# SO-8-normal.net
KiCad netlist of a schematic drawn in EAGLE
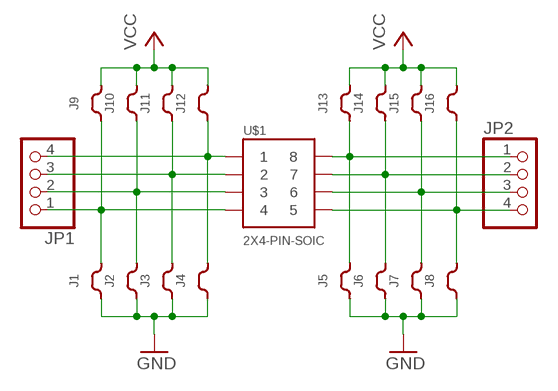
[diagram p0: schematic, sheet 1]

(export (version "E")
  (design (tool "Eeschema 10.0.6"))
  (components
    (comp (ref "J1")
      (value "JUMPER-0805")
      (footprint "eagle-import:RCLJ-0805")
      (libsource (lib "eagle-import") (part "JUMPER-0805"))
    )
    (comp (ref "J2")
      (value "JUMPER-0805")
      (footprint "eagle-import:RCLJ-0805")
      (libsource (lib "eagle-import") (part "JUMPER-0805"))
    )
    (comp (ref "J3")
      (value "JUMPER-0805")
      (footprint "eagle-import:RCLJ-0805")
      (libsource (lib "eagle-import") (part "JUMPER-0805"))
    )
    (comp (ref "J4")
      (value "JUMPER-0805")
      (footprint "eagle-import:RCLJ-0805")
      (libsource (lib "eagle-import") (part "JUMPER-0805"))
    )
    (comp (ref "J5")
      (value "JUMPER-0805")
      (footprint "eagle-import:RCLJ-0805")
      (libsource (lib "eagle-import") (part "JUMPER-0805"))
    )
    (comp (ref "J6")
      (value "JUMPER-0805")
      (footprint "eagle-import:RCLJ-0805")
      (libsource (lib "eagle-import") (part "JUMPER-0805"))
    )
    (comp (ref "J7")
      (value "JUMPER-0805")
      (footprint "eagle-import:RCLJ-0805")
      (libsource (lib "eagle-import") (part "JUMPER-0805"))
    )
    (comp (ref "J8")
      (value "JUMPER-0805")
      (footprint "eagle-import:RCLJ-0805")
      (libsource (lib "eagle-import") (part "JUMPER-0805"))
    )
    (comp (ref "J9")
      (value "JUMPER-0603")
      (footprint "eagle-import:RCLJ-0603")
      (libsource (lib "eagle-import") (part "JUMPER-0603"))
    )
    (comp (ref "J10")
      (value "JUMPER-0603")
      (footprint "eagle-import:RCLJ-0603")
      (libsource (lib "eagle-import") (part "JUMPER-0603"))
    )
    (comp (ref "J11")
      (value "JUMPER-0603")
      (footprint "eagle-import:RCLJ-0603")
      (libsource (lib "eagle-import") (part "JUMPER-0603"))
    )
    (comp (ref "J12")
      (value "JUMPER-0603")
      (footprint "eagle-import:RCLJ-0603")
      (libsource (lib "eagle-import") (part "JUMPER-0603"))
    )
    (comp (ref "J13")
      (value "JUMPER-0603")
      (footprint "eagle-import:RCLJ-0603")
      (libsource (lib "eagle-import") (part "JUMPER-0603"))
    )
    (comp (ref "J14")
      (value "JUMPER-0603")
      (footprint "eagle-import:RCLJ-0603")
      (libsource (lib "eagle-import") (part "JUMPER-0603"))
    )
    (comp (ref "J15")
      (value "JUMPER-0603")
      (footprint "eagle-import:RCLJ-0603")
      (libsource (lib "eagle-import") (part "JUMPER-0603"))
    )
    (comp (ref "J16")
      (value "JUMPER-0603")
      (footprint "eagle-import:RCLJ-0603")
      (libsource (lib "eagle-import") (part "JUMPER-0603"))
    )
    (comp (ref "JP1")
      (value "PINHD-1X4")
      (footprint "eagle-import:1X04")
      (libsource (lib "eagle-import") (part "PINHD-1X4"))
    )
    (comp (ref "JP2")
      (value "PINHD-1X4")
      (footprint "eagle-import:1X04")
      (libsource (lib "eagle-import") (part "PINHD-1X4"))
    )
    (comp (ref "U$1")
      (value "2X4-PIN-SOIC")
      (footprint "eagle-import:SO8")
      (libsource (lib "eagle-import") (part "2X4-PIN-SOIC"))
    )
  )
  (nets
    (net (code "1") (name "GND") (class "Default")
      (node (ref "J1") (pin "1") (pinfunction "P$1_1") (pintype "bidirectional"))
      (node (ref "J2") (pin "1") (pinfunction "P$1_1") (pintype "bidirectional"))
      (node (ref "J3") (pin "1") (pinfunction "P$1_1") (pintype "bidirectional"))
      (node (ref "J4") (pin "1") (pinfunction "P$1_1") (pintype "bidirectional"))
      (node (ref "J5") (pin "1") (pinfunction "P$1_1") (pintype "bidirectional"))
      (node (ref "J6") (pin "1") (pinfunction "P$1_1") (pintype "bidirectional"))
      (node (ref "J7") (pin "1") (pinfunction "P$1_1") (pintype "bidirectional"))
      (node (ref "J8") (pin "1") (pinfunction "P$1_1") (pintype "bidirectional"))
    )
    (net (code "2") (name "Net-(J1-P$2)") (class "Default")
      (node (ref "J1") (pin "2") (pinfunction "P$2_2") (pintype "bidirectional"))
      (node (ref "J9") (pin "1") (pinfunction "P$1_1") (pintype "bidirectional"))
      (node (ref "JP1") (pin "1") (pinfunction "1_1") (pintype "passive"))
      (node (ref "U$1") (pin "P$4") (pinfunction "4_P$4") (pintype "bidirectional"))
    )
    (net (code "3") (name "Net-(J10-P$1)") (class "Default")
      (node (ref "J10") (pin "1") (pinfunction "P$1_1") (pintype "bidirectional"))
      (node (ref "J2") (pin "2") (pinfunction "P$2_2") (pintype "bidirectional"))
      (node (ref "JP1") (pin "2") (pinfunction "2_2") (pintype "passive"))
      (node (ref "U$1") (pin "P$3") (pinfunction "3_P$3") (pintype "bidirectional"))
    )
    (net (code "4") (name "Net-(J11-P$1)") (class "Default")
      (node (ref "J11") (pin "1") (pinfunction "P$1_1") (pintype "bidirectional"))
      (node (ref "J3") (pin "2") (pinfunction "P$2_2") (pintype "bidirectional"))
      (node (ref "JP1") (pin "3") (pinfunction "3_3") (pintype "passive"))
      (node (ref "U$1") (pin "P$2") (pinfunction "2_P$2") (pintype "bidirectional"))
    )
    (net (code "5") (name "Net-(J12-P$1)") (class "Default")
      (node (ref "J12") (pin "1") (pinfunction "P$1_1") (pintype "bidirectional"))
      (node (ref "J4") (pin "2") (pinfunction "P$2_2") (pintype "bidirectional"))
      (node (ref "JP1") (pin "4") (pinfunction "4_4") (pintype "passive"))
      (node (ref "U$1") (pin "P$1") (pinfunction "1_P$1") (pintype "bidirectional"))
    )
    (net (code "6") (name "Net-(J13-P$1)") (class "Default")
      (node (ref "J13") (pin "1") (pinfunction "P$1_1") (pintype "bidirectional"))
      (node (ref "J5") (pin "2") (pinfunction "P$2_2") (pintype "bidirectional"))
      (node (ref "JP2") (pin "1") (pinfunction "1_1") (pintype "passive"))
      (node (ref "U$1") (pin "P$8") (pinfunction "8_P$8") (pintype "bidirectional"))
    )
    (net (code "7") (name "Net-(J14-P$1)") (class "Default")
      (node (ref "J14") (pin "1") (pinfunction "P$1_1") (pintype "bidirectional"))
      (node (ref "J6") (pin "2") (pinfunction "P$2_2") (pintype "bidirectional"))
      (node (ref "JP2") (pin "2") (pinfunction "2_2") (pintype "passive"))
      (node (ref "U$1") (pin "P$7") (pinfunction "7_P$7") (pintype "bidirectional"))
    )
    (net (code "8") (name "Net-(J15-P$1)") (class "Default")
      (node (ref "J15") (pin "1") (pinfunction "P$1_1") (pintype "bidirectional"))
      (node (ref "J7") (pin "2") (pinfunction "P$2_2") (pintype "bidirectional"))
      (node (ref "JP2") (pin "3") (pinfunction "3_3") (pintype "passive"))
      (node (ref "U$1") (pin "P$6") (pinfunction "6_P$6") (pintype "bidirectional"))
    )
    (net (code "9") (name "Net-(J16-P$1)") (class "Default")
      (node (ref "J16") (pin "1") (pinfunction "P$1_1") (pintype "bidirectional"))
      (node (ref "J8") (pin "2") (pinfunction "P$2_2") (pintype "bidirectional"))
      (node (ref "JP2") (pin "4") (pinfunction "4_4") (pintype "passive"))
      (node (ref "U$1") (pin "P$5") (pinfunction "5_P$5") (pintype "bidirectional"))
    )
    (net (code "10") (name "VCC") (class "Default")
      (node (ref "J10") (pin "2") (pinfunction "P$2_2") (pintype "bidirectional"))
      (node (ref "J11") (pin "2") (pinfunction "P$2_2") (pintype "bidirectional"))
      (node (ref "J12") (pin "2") (pinfunction "P$2_2") (pintype "bidirectional"))
      (node (ref "J13") (pin "2") (pinfunction "P$2_2") (pintype "bidirectional"))
      (node (ref "J14") (pin "2") (pinfunction "P$2_2") (pintype "bidirectional"))
      (node (ref "J15") (pin "2") (pinfunction "P$2_2") (pintype "bidirectional"))
      (node (ref "J16") (pin "2") (pinfunction "P$2_2") (pintype "bidirectional"))
      (node (ref "J9") (pin "2") (pinfunction "P$2_2") (pintype "bidirectional"))
    )
  )
)
